# Syno_Ver3_0.net
KiCad netlist of a schematic drawn in EAGLE
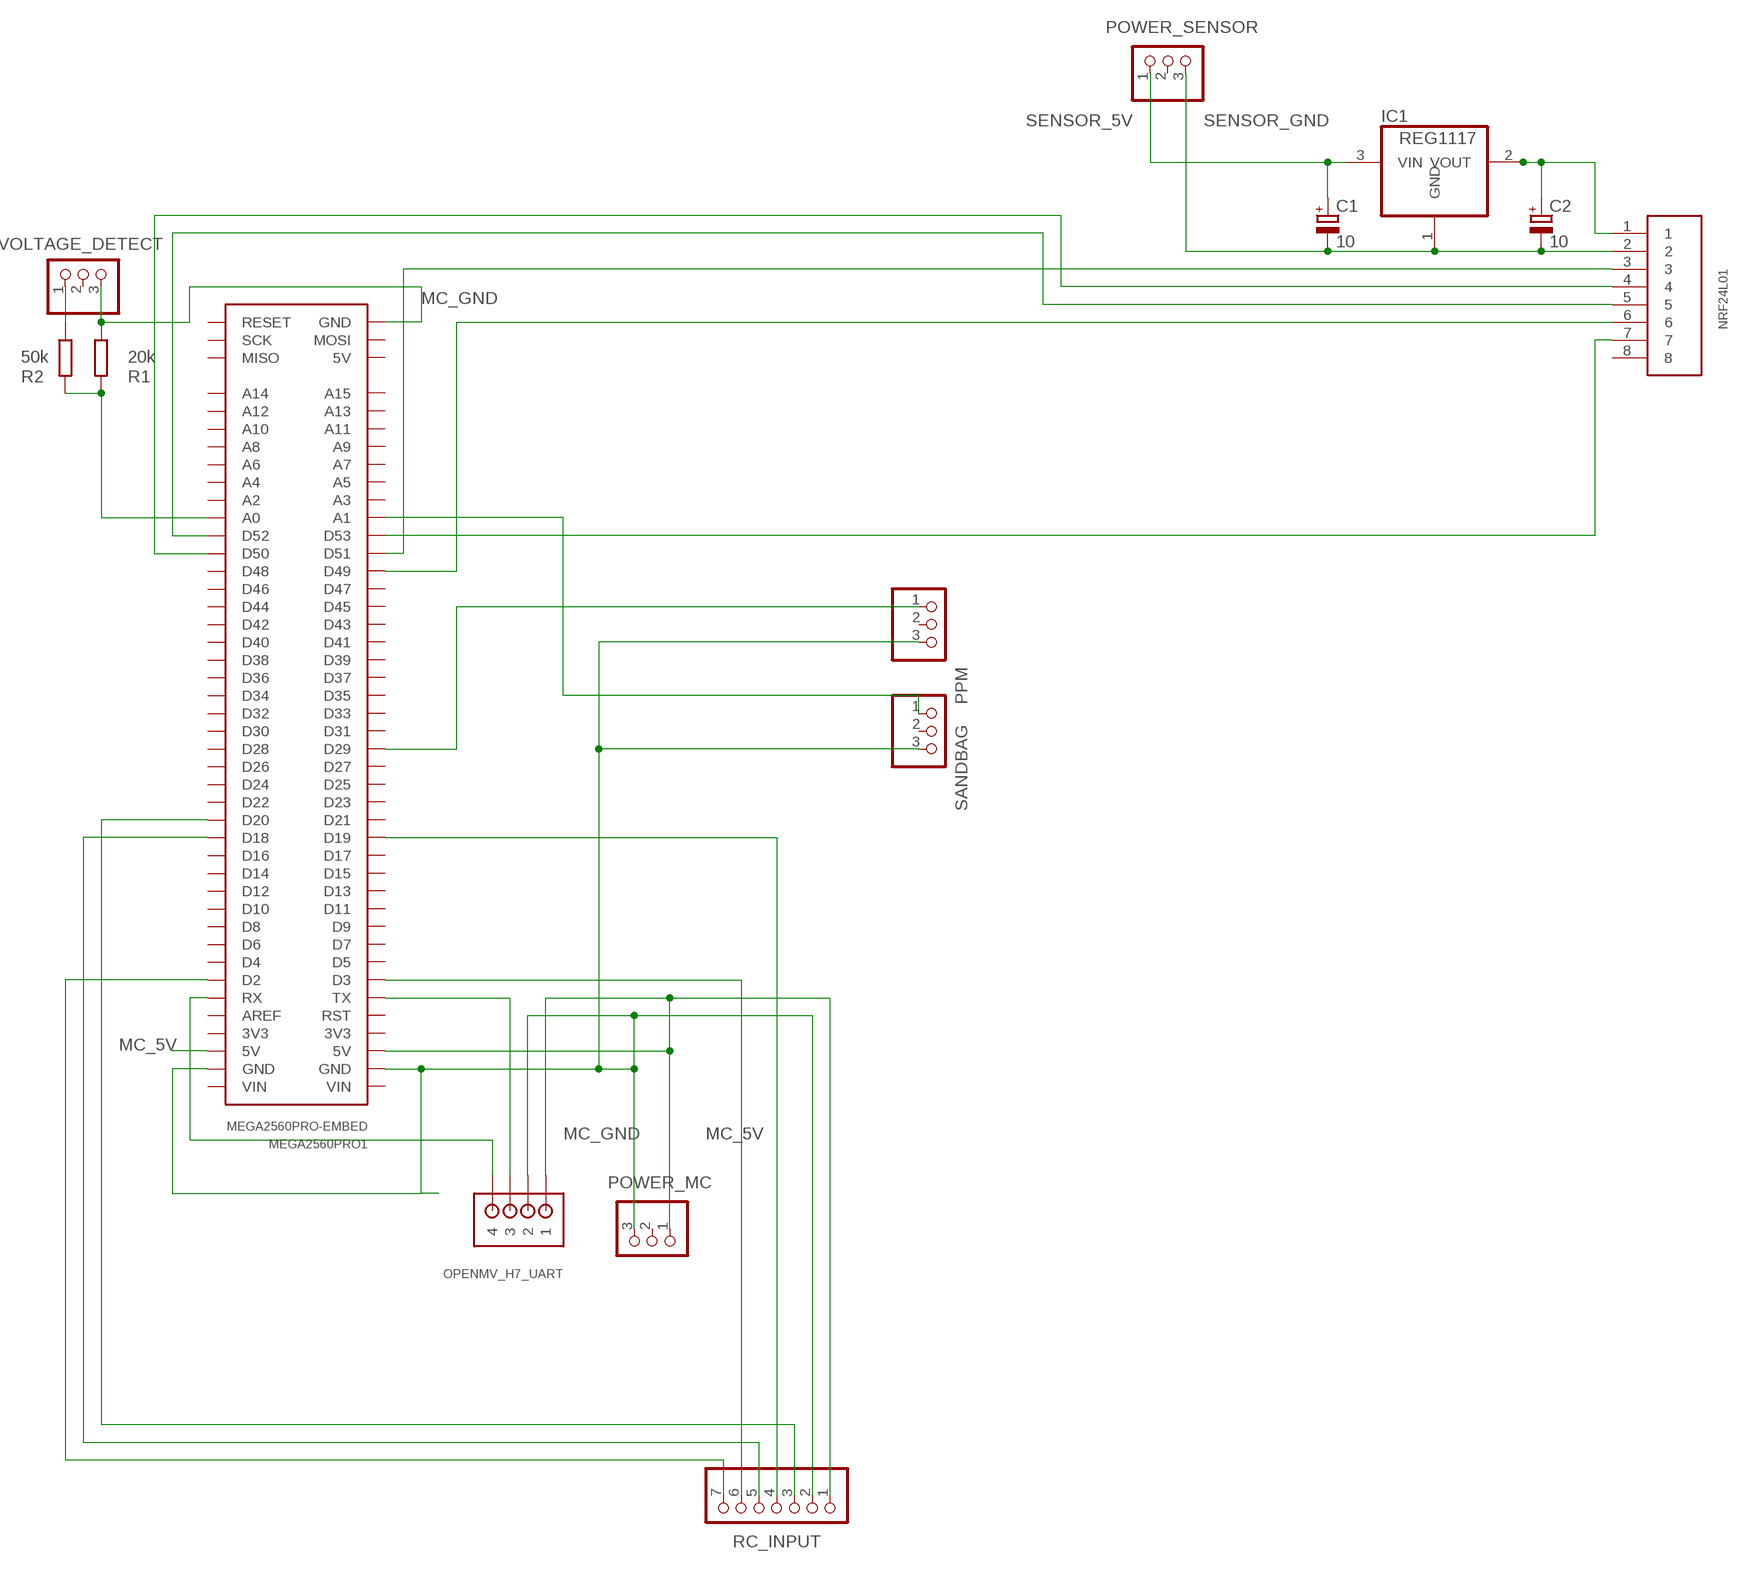
[diagram p0: schematic, sheet 1]

(export (version "E")
  (design (tool "Eeschema 10.0.6"))
  (components
    (comp (ref "C1")
      (value "10")
      (footprint "eagle-import:E1,8-4")
      (libsource (lib "eagle-import") (part "CPOL-EUE1.8-4"))
    )
    (comp (ref "C2")
      (value "10")
      (footprint "eagle-import:E1,8-4")
      (libsource (lib "eagle-import") (part "CPOL-EUE1.8-4"))
    )
    (comp (ref "IC1")
      (value "REG1117")
      (footprint "eagle-import:SOT223")
      (libsource (lib "eagle-import") (part "REG1117"))
    )
    (comp (ref "MEGA2560PRO1")
      (value "MEGA2560PRO-EMBED")
      (footprint "eagle-import:MEGA2560PRO-EMBED")
      (libsource (lib "eagle-import") (part "MEGA2560PRO-EMBED"))
    )
    (comp (ref "NRF24L01")
      (value "8PIN")
      (footprint "eagle-import:B8B-PH-K-S")
      (libsource (lib "eagle-import") (part "8PIN"))
    )
    (comp (ref "OPENMV_H7_UART")
      (value "JST-PH_4-PIN_HEADER")
      (footprint "eagle-import:JST_B4B-PH_HEADER")
      (libsource (lib "eagle-import") (part "JST-PH_4-PIN_HEADER"))
    )
    (comp (ref "POWER_MC")
      (value "PINHD-1X3/90")
      (footprint "eagle-import:1X03_90")
      (libsource (lib "eagle-import") (part "PINHD-1X3/90"))
    )
    (comp (ref "POWER_SENSOR")
      (value "PINHD-1X3/90")
      (footprint "eagle-import:1X03_90")
      (libsource (lib "eagle-import") (part "PINHD-1X3/90"))
    )
    (comp (ref "PPM")
      (value "PINHD-1X3/90")
      (footprint "eagle-import:1X03_90")
      (libsource (lib "eagle-import") (part "PINHD-1X3/90"))
    )
    (comp (ref "R1")
      (value "20k")
      (footprint "eagle-import:0204_5")
      (libsource (lib "eagle-import") (part "R-EU_0204/5"))
    )
    (comp (ref "R2")
      (value "50k")
      (footprint "eagle-import:0204_5")
      (libsource (lib "eagle-import") (part "R-EU_0204/5"))
    )
    (comp (ref "RC_INPUT")
      (value "PINHD-1X7/90")
      (footprint "eagle-import:1X07_90")
      (libsource (lib "eagle-import") (part "PINHD-1X7/90"))
    )
    (comp (ref "SANDBAG")
      (value "PINHD-1X3/90")
      (footprint "eagle-import:1X03_90")
      (libsource (lib "eagle-import") (part "PINHD-1X3/90"))
    )
    (comp (ref "VOLTAGE_DETECT")
      (value "PINHD-1X3/90")
      (footprint "eagle-import:1X03_90")
      (libsource (lib "eagle-import") (part "PINHD-1X3/90"))
    )
  )
  (nets
    (net (code "1") (name "/MC_5V") (class "Default")
      (node (ref "MEGA2560PRO1") (pin "5V@1") (pinfunction "5V_5V@1") (pintype "bidirectional"))
      (node (ref "MEGA2560PRO1") (pin "5V@2") (pinfunction "5V_5V@2") (pintype "bidirectional"))
      (node (ref "OPENMV_H7_UART") (pin "P1") (pinfunction "1_P1") (pintype "bidirectional"))
      (node (ref "POWER_MC") (pin "1") (pinfunction "1_1") (pintype "passive"))
      (node (ref "RC_INPUT") (pin "1") (pinfunction "1_1") (pintype "passive"))
    )
    (net (code "2") (name "/MC_GND") (class "Default")
      (node (ref "MEGA2560PRO1") (pin "GND@1") (pinfunction "GND_GND@1") (pintype "bidirectional"))
      (node (ref "MEGA2560PRO1") (pin "GND@2") (pinfunction "GND_GND@2") (pintype "bidirectional"))
      (node (ref "MEGA2560PRO1") (pin "GND@3") (pinfunction "GND_GND@3") (pintype "bidirectional"))
      (node (ref "OPENMV_H7_UART") (pin "P2") (pinfunction "2_P2") (pintype "bidirectional"))
      (node (ref "POWER_MC") (pin "3") (pinfunction "3_3") (pintype "passive"))
      (node (ref "PPM") (pin "3") (pinfunction "3_3") (pintype "passive"))
      (node (ref "R1") (pin "1") (pinfunction "1_1") (pintype "passive"))
      (node (ref "RC_INPUT") (pin "2") (pinfunction "2_2") (pintype "passive"))
      (node (ref "SANDBAG") (pin "3") (pinfunction "3_3") (pintype "passive"))
      (node (ref "VOLTAGE_DETECT") (pin "3") (pinfunction "3_3") (pintype "passive"))
    )
    (net (code "3") (name "/SENSOR_5V") (class "Default")
      (node (ref "C1") (pin "+") (pinfunction "+_+") (pintype "passive"))
      (node (ref "IC1") (pin "3") (pinfunction "VIN_3") (pintype "input"))
      (node (ref "POWER_SENSOR") (pin "1") (pinfunction "1_1") (pintype "passive"))
    )
    (net (code "4") (name "/SENSOR_GND") (class "Default")
      (node (ref "C1") (pin "-") (pinfunction "-_-") (pintype "passive"))
      (node (ref "C2") (pin "-") (pinfunction "-_-") (pintype "passive"))
      (node (ref "IC1") (pin "1") (pinfunction "GND_1") (pintype "power_in"))
      (node (ref "NRF24L01") (pin "2") (pinfunction "2_2") (pintype "bidirectional"))
      (node (ref "POWER_SENSOR") (pin "3") (pinfunction "3_3") (pintype "passive"))
    )
    (net (code "5") (name "Net-(IC1-VOUT)") (class "Default")
      (node (ref "C2") (pin "+") (pinfunction "+_+") (pintype "passive"))
      (node (ref "IC1") (pin "2") (pinfunction "VOUT_2") (pintype "output"))
      (node (ref "NRF24L01") (pin "1") (pinfunction "1_1") (pintype "bidirectional"))
    )
    (net (code "6") (name "Net-(MEGA2560PRO1-PadA0)") (class "Default")
      (node (ref "MEGA2560PRO1") (pin "A0") (pinfunction "A0_A0") (pintype "bidirectional"))
      (node (ref "R1") (pin "2") (pinfunction "2_2") (pintype "passive"))
      (node (ref "R2") (pin "2") (pinfunction "2_2") (pintype "passive"))
    )
    (net (code "7") (name "Net-(MEGA2560PRO1-PadA1)") (class "Default")
      (node (ref "MEGA2560PRO1") (pin "A1") (pinfunction "A1_A1") (pintype "bidirectional"))
      (node (ref "SANDBAG") (pin "1") (pinfunction "1_1") (pintype "passive"))
    )
    (net (code "8") (name "Net-(MEGA2560PRO1-PadD2)") (class "Default")
      (node (ref "MEGA2560PRO1") (pin "D2") (pinfunction "D2_D2") (pintype "bidirectional"))
      (node (ref "RC_INPUT") (pin "7") (pinfunction "7_7") (pintype "passive"))
    )
    (net (code "9") (name "Net-(MEGA2560PRO1-PadD3)") (class "Default")
      (node (ref "MEGA2560PRO1") (pin "D3") (pinfunction "D3_D3") (pintype "bidirectional"))
      (node (ref "RC_INPUT") (pin "6") (pinfunction "6_6") (pintype "passive"))
    )
    (net (code "10") (name "Net-(MEGA2560PRO1-PadD18)") (class "Default")
      (node (ref "MEGA2560PRO1") (pin "D18") (pinfunction "D18_D18") (pintype "bidirectional"))
      (node (ref "RC_INPUT") (pin "5") (pinfunction "5_5") (pintype "passive"))
    )
    (net (code "11") (name "Net-(MEGA2560PRO1-PadD19)") (class "Default")
      (node (ref "MEGA2560PRO1") (pin "D19") (pinfunction "D19_D19") (pintype "bidirectional"))
      (node (ref "RC_INPUT") (pin "4") (pinfunction "4_4") (pintype "passive"))
    )
    (net (code "12") (name "Net-(MEGA2560PRO1-PadD20)") (class "Default")
      (node (ref "MEGA2560PRO1") (pin "D20") (pinfunction "D20_D20") (pintype "bidirectional"))
      (node (ref "RC_INPUT") (pin "3") (pinfunction "3_3") (pintype "passive"))
    )
    (net (code "13") (name "Net-(MEGA2560PRO1-PadD29)") (class "Default")
      (node (ref "MEGA2560PRO1") (pin "D29") (pinfunction "D29_D29") (pintype "bidirectional"))
      (node (ref "PPM") (pin "1") (pinfunction "1_1") (pintype "passive"))
    )
    (net (code "14") (name "Net-(MEGA2560PRO1-PadD49)") (class "Default")
      (node (ref "MEGA2560PRO1") (pin "D49") (pinfunction "D49_D49") (pintype "bidirectional"))
      (node (ref "NRF24L01") (pin "6") (pinfunction "6_6") (pintype "bidirectional"))
    )
    (net (code "15") (name "Net-(MEGA2560PRO1-PadD50)") (class "Default")
      (node (ref "MEGA2560PRO1") (pin "D50") (pinfunction "D50_D50") (pintype "bidirectional"))
      (node (ref "NRF24L01") (pin "4") (pinfunction "4_4") (pintype "bidirectional"))
    )
    (net (code "16") (name "Net-(MEGA2560PRO1-PadD51)") (class "Default")
      (node (ref "MEGA2560PRO1") (pin "D51") (pinfunction "D51_D51") (pintype "bidirectional"))
      (node (ref "NRF24L01") (pin "3") (pinfunction "3_3") (pintype "bidirectional"))
    )
    (net (code "17") (name "Net-(MEGA2560PRO1-PadD52)") (class "Default")
      (node (ref "MEGA2560PRO1") (pin "D52") (pinfunction "D52_D52") (pintype "bidirectional"))
      (node (ref "NRF24L01") (pin "5") (pinfunction "5_5") (pintype "bidirectional"))
    )
    (net (code "18") (name "Net-(MEGA2560PRO1-PadD53)") (class "Default")
      (node (ref "MEGA2560PRO1") (pin "D53") (pinfunction "D53_D53") (pintype "bidirectional"))
      (node (ref "NRF24L01") (pin "7") (pinfunction "7_7") (pintype "bidirectional"))
    )
    (net (code "19") (name "Net-(OPENMV_H7_UART-3)") (class "Default")
      (node (ref "MEGA2560PRO1") (pin "TX") (pinfunction "TX_TX") (pintype "bidirectional"))
      (node (ref "OPENMV_H7_UART") (pin "P3") (pinfunction "3_P3") (pintype "bidirectional"))
    )
    (net (code "20") (name "Net-(OPENMV_H7_UART-4)") (class "Default")
      (node (ref "MEGA2560PRO1") (pin "RX") (pinfunction "RX_RX") (pintype "bidirectional"))
      (node (ref "OPENMV_H7_UART") (pin "P4") (pinfunction "4_P4") (pintype "bidirectional"))
    )
    (net (code "21") (name "Net-(R2-Pad1)") (class "Default")
      (node (ref "R2") (pin "1") (pinfunction "1_1") (pintype "passive"))
      (node (ref "VOLTAGE_DETECT") (pin "1") (pinfunction "1_1") (pintype "passive"))
    )
    (net (code "22") (name "unconnected-(MEGA2560PRO1-3V3-Pad3V3@1)") (class "Default")
      (node (ref "MEGA2560PRO1") (pin "3V3@1") (pinfunction "3V3_3V3@1") (pintype "bidirectional"))
    )
    (net (code "23") (name "unconnected-(MEGA2560PRO1-3V3-Pad3V3@2)") (class "Default")
      (node (ref "MEGA2560PRO1") (pin "3V3@2") (pinfunction "3V3_3V3@2") (pintype "bidirectional"))
    )
    (net (code "24") (name "unconnected-(MEGA2560PRO1-5V-Pad5V@3)") (class "Default")
      (node (ref "MEGA2560PRO1") (pin "5V@3") (pinfunction "5V_5V@3") (pintype "bidirectional"))
    )
    (net (code "25") (name "unconnected-(MEGA2560PRO1-PadA2)") (class "Default")
      (node (ref "MEGA2560PRO1") (pin "A2") (pinfunction "A2_A2") (pintype "bidirectional"))
    )
    (net (code "26") (name "unconnected-(MEGA2560PRO1-PadA3)") (class "Default")
      (node (ref "MEGA2560PRO1") (pin "A3") (pinfunction "A3_A3") (pintype "bidirectional"))
    )
    (net (code "27") (name "unconnected-(MEGA2560PRO1-PadA4)") (class "Default")
      (node (ref "MEGA2560PRO1") (pin "A4") (pinfunction "A4_A4") (pintype "bidirectional"))
    )
    (net (code "28") (name "unconnected-(MEGA2560PRO1-PadA5)") (class "Default")
      (node (ref "MEGA2560PRO1") (pin "A5") (pinfunction "A5_A5") (pintype "bidirectional"))
    )
    (net (code "29") (name "unconnected-(MEGA2560PRO1-PadA6)") (class "Default")
      (node (ref "MEGA2560PRO1") (pin "A6") (pinfunction "A6_A6") (pintype "bidirectional"))
    )
    (net (code "30") (name "unconnected-(MEGA2560PRO1-PadA7)") (class "Default")
      (node (ref "MEGA2560PRO1") (pin "A7") (pinfunction "A7_A7") (pintype "bidirectional"))
    )
    (net (code "31") (name "unconnected-(MEGA2560PRO1-PadA8)") (class "Default")
      (node (ref "MEGA2560PRO1") (pin "A8") (pinfunction "A8_A8") (pintype "bidirectional"))
    )
    (net (code "32") (name "unconnected-(MEGA2560PRO1-PadA9)") (class "Default")
      (node (ref "MEGA2560PRO1") (pin "A9") (pinfunction "A9_A9") (pintype "bidirectional"))
    )
    (net (code "33") (name "unconnected-(MEGA2560PRO1-PadA10)") (class "Default")
      (node (ref "MEGA2560PRO1") (pin "A10") (pinfunction "A10_A10") (pintype "bidirectional"))
    )
    (net (code "34") (name "unconnected-(MEGA2560PRO1-PadA11)") (class "Default")
      (node (ref "MEGA2560PRO1") (pin "A11") (pinfunction "A11_A11") (pintype "bidirectional"))
    )
    (net (code "35") (name "unconnected-(MEGA2560PRO1-PadA12)") (class "Default")
      (node (ref "MEGA2560PRO1") (pin "A12") (pinfunction "A12_A12") (pintype "bidirectional"))
    )
    (net (code "36") (name "unconnected-(MEGA2560PRO1-PadA13)") (class "Default")
      (node (ref "MEGA2560PRO1") (pin "A13") (pinfunction "A13_A13") (pintype "bidirectional"))
    )
    (net (code "37") (name "unconnected-(MEGA2560PRO1-PadA14)") (class "Default")
      (node (ref "MEGA2560PRO1") (pin "A14") (pinfunction "A14_A14") (pintype "bidirectional"))
    )
    (net (code "38") (name "unconnected-(MEGA2560PRO1-PadA15)") (class "Default")
      (node (ref "MEGA2560PRO1") (pin "A15") (pinfunction "A15_A15") (pintype "bidirectional"))
    )
    (net (code "39") (name "unconnected-(MEGA2560PRO1-PadAREF)") (class "Default")
      (node (ref "MEGA2560PRO1") (pin "AREF") (pinfunction "AREF_AREF") (pintype "bidirectional"))
    )
    (net (code "40") (name "unconnected-(MEGA2560PRO1-PadD4)") (class "Default")
      (node (ref "MEGA2560PRO1") (pin "D4") (pinfunction "D4_D4") (pintype "bidirectional"))
    )
    (net (code "41") (name "unconnected-(MEGA2560PRO1-PadD5)") (class "Default")
      (node (ref "MEGA2560PRO1") (pin "D5") (pinfunction "D5_D5") (pintype "bidirectional"))
    )
    (net (code "42") (name "unconnected-(MEGA2560PRO1-PadD6)") (class "Default")
      (node (ref "MEGA2560PRO1") (pin "D6") (pinfunction "D6_D6") (pintype "bidirectional"))
    )
    (net (code "43") (name "unconnected-(MEGA2560PRO1-PadD7)") (class "Default")
      (node (ref "MEGA2560PRO1") (pin "D7") (pinfunction "D7_D7") (pintype "bidirectional"))
    )
    (net (code "44") (name "unconnected-(MEGA2560PRO1-PadD8)") (class "Default")
      (node (ref "MEGA2560PRO1") (pin "D8") (pinfunction "D8_D8") (pintype "bidirectional"))
    )
    (net (code "45") (name "unconnected-(MEGA2560PRO1-PadD9)") (class "Default")
      (node (ref "MEGA2560PRO1") (pin "D9") (pinfunction "D9_D9") (pintype "bidirectional"))
    )
    (net (code "46") (name "unconnected-(MEGA2560PRO1-PadD10)") (class "Default")
      (node (ref "MEGA2560PRO1") (pin "D10") (pinfunction "D10_D10") (pintype "bidirectional"))
    )
    (net (code "47") (name "unconnected-(MEGA2560PRO1-PadD11)") (class "Default")
      (node (ref "MEGA2560PRO1") (pin "D11") (pinfunction "D11_D11") (pintype "bidirectional"))
    )
    (net (code "48") (name "unconnected-(MEGA2560PRO1-PadD12)") (class "Default")
      (node (ref "MEGA2560PRO1") (pin "D12") (pinfunction "D12_D12") (pintype "bidirectional"))
    )
    (net (code "49") (name "unconnected-(MEGA2560PRO1-PadD13)") (class "Default")
      (node (ref "MEGA2560PRO1") (pin "D13") (pinfunction "D13_D13") (pintype "bidirectional"))
    )
    (net (code "50") (name "unconnected-(MEGA2560PRO1-PadD14)") (class "Default")
      (node (ref "MEGA2560PRO1") (pin "D14") (pinfunction "D14_D14") (pintype "bidirectional"))
    )
    (net (code "51") (name "unconnected-(MEGA2560PRO1-PadD15)") (class "Default")
      (node (ref "MEGA2560PRO1") (pin "D15") (pinfunction "D15_D15") (pintype "bidirectional"))
    )
    (net (code "52") (name "unconnected-(MEGA2560PRO1-PadD16)") (class "Default")
      (node (ref "MEGA2560PRO1") (pin "D16") (pinfunction "D16_D16") (pintype "bidirectional"))
    )
    (net (code "53") (name "unconnected-(MEGA2560PRO1-PadD17)") (class "Default")
      (node (ref "MEGA2560PRO1") (pin "D17") (pinfunction "D17_D17") (pintype "bidirectional"))
    )
    (net (code "54") (name "unconnected-(MEGA2560PRO1-PadD21)") (class "Default")
      (node (ref "MEGA2560PRO1") (pin "D21") (pinfunction "D21_D21") (pintype "bidirectional"))
    )
    (net (code "55") (name "unconnected-(MEGA2560PRO1-PadD22)") (class "Default")
      (node (ref "MEGA2560PRO1") (pin "D22") (pinfunction "D22_D22") (pintype "bidirectional"))
    )
    (net (code "56") (name "unconnected-(MEGA2560PRO1-PadD23)") (class "Default")
      (node (ref "MEGA2560PRO1") (pin "D23") (pinfunction "D23_D23") (pintype "bidirectional"))
    )
    (net (code "57") (name "unconnected-(MEGA2560PRO1-PadD24)") (class "Default")
      (node (ref "MEGA2560PRO1") (pin "D24") (pinfunction "D24_D24") (pintype "bidirectional"))
    )
    (net (code "58") (name "unconnected-(MEGA2560PRO1-PadD25)") (class "Default")
      (node (ref "MEGA2560PRO1") (pin "D25") (pinfunction "D25_D25") (pintype "bidirectional"))
    )
    (net (code "59") (name "unconnected-(MEGA2560PRO1-PadD26)") (class "Default")
      (node (ref "MEGA2560PRO1") (pin "D26") (pinfunction "D26_D26") (pintype "bidirectional"))
    )
    (net (code "60") (name "unconnected-(MEGA2560PRO1-PadD27)") (class "Default")
      (node (ref "MEGA2560PRO1") (pin "D27") (pinfunction "D27_D27") (pintype "bidirectional"))
    )
    (net (code "61") (name "unconnected-(MEGA2560PRO1-PadD28)") (class "Default")
      (node (ref "MEGA2560PRO1") (pin "D28") (pinfunction "D28_D28") (pintype "bidirectional"))
    )
    (net (code "62") (name "unconnected-(MEGA2560PRO1-PadD30)") (class "Default")
      (node (ref "MEGA2560PRO1") (pin "D30") (pinfunction "D30_D30") (pintype "bidirectional"))
    )
    (net (code "63") (name "unconnected-(MEGA2560PRO1-PadD31)") (class "Default")
      (node (ref "MEGA2560PRO1") (pin "D31") (pinfunction "D31_D31") (pintype "bidirectional"))
    )
    (net (code "64") (name "unconnected-(MEGA2560PRO1-PadD32)") (class "Default")
      (node (ref "MEGA2560PRO1") (pin "D32") (pinfunction "D32_D32") (pintype "bidirectional"))
    )
    (net (code "65") (name "unconnected-(MEGA2560PRO1-PadD33)") (class "Default")
      (node (ref "MEGA2560PRO1") (pin "D33") (pinfunction "D33_D33") (pintype "bidirectional"))
    )
    (net (code "66") (name "unconnected-(MEGA2560PRO1-PadD34)") (class "Default")
      (node (ref "MEGA2560PRO1") (pin "D34") (pinfunction "D34_D34") (pintype "bidirectional"))
    )
    (net (code "67") (name "unconnected-(MEGA2560PRO1-PadD35)") (class "Default")
      (node (ref "MEGA2560PRO1") (pin "D35") (pinfunction "D35_D35") (pintype "bidirectional"))
    )
    (net (code "68") (name "unconnected-(MEGA2560PRO1-PadD36)") (class "Default")
      (node (ref "MEGA2560PRO1") (pin "D36") (pinfunction "D36_D36") (pintype "bidirectional"))
    )
    (net (code "69") (name "unconnected-(MEGA2560PRO1-PadD37)") (class "Default")
      (node (ref "MEGA2560PRO1") (pin "D37") (pinfunction "D37_D37") (pintype "bidirectional"))
    )
    (net (code "70") (name "unconnected-(MEGA2560PRO1-PadD38)") (class "Default")
      (node (ref "MEGA2560PRO1") (pin "D38") (pinfunction "D38_D38") (pintype "bidirectional"))
    )
    (net (code "71") (name "unconnected-(MEGA2560PRO1-PadD39)") (class "Default")
      (node (ref "MEGA2560PRO1") (pin "D39") (pinfunction "D39_D39") (pintype "bidirectional"))
    )
    (net (code "72") (name "unconnected-(MEGA2560PRO1-PadD40)") (class "Default")
      (node (ref "MEGA2560PRO1") (pin "D40") (pinfunction "D40_D40") (pintype "bidirectional"))
    )
    (net (code "73") (name "unconnected-(MEGA2560PRO1-PadD41)") (class "Default")
      (node (ref "MEGA2560PRO1") (pin "D41") (pinfunction "D41_D41") (pintype "bidirectional"))
    )
    (net (code "74") (name "unconnected-(MEGA2560PRO1-PadD42)") (class "Default")
      (node (ref "MEGA2560PRO1") (pin "D42") (pinfunction "D42_D42") (pintype "bidirectional"))
    )
    (net (code "75") (name "unconnected-(MEGA2560PRO1-PadD43)") (class "Default")
      (node (ref "MEGA2560PRO1") (pin "D43") (pinfunction "D43_D43") (pintype "bidirectional"))
    )
    (net (code "76") (name "unconnected-(MEGA2560PRO1-PadD44)") (class "Default")
      (node (ref "MEGA2560PRO1") (pin "D44") (pinfunction "D44_D44") (pintype "bidirectional"))
    )
    (net (code "77") (name "unconnected-(MEGA2560PRO1-PadD45)") (class "Default")
      (node (ref "MEGA2560PRO1") (pin "D45") (pinfunction "D45_D45") (pintype "bidirectional"))
    )
    (net (code "78") (name "unconnected-(MEGA2560PRO1-PadD46)") (class "Default")
      (node (ref "MEGA2560PRO1") (pin "D46") (pinfunction "D46_D46") (pintype "bidirectional"))
    )
    (net (code "79") (name "unconnected-(MEGA2560PRO1-PadD47)") (class "Default")
      (node (ref "MEGA2560PRO1") (pin "D47") (pinfunction "D47_D47") (pintype "bidirectional"))
    )
    (net (code "80") (name "unconnected-(MEGA2560PRO1-PadD48)") (class "Default")
      (node (ref "MEGA2560PRO1") (pin "D48") (pinfunction "D48_D48") (pintype "bidirectional"))
    )
    (net (code "81") (name "unconnected-(MEGA2560PRO1-PadMISO)") (class "Default")
      (node (ref "MEGA2560PRO1") (pin "MISO") (pinfunction "MISO_MISO") (pintype "bidirectional"))
    )
    (net (code "82") (name "unconnected-(MEGA2560PRO1-PadMOSI)") (class "Default")
      (node (ref "MEGA2560PRO1") (pin "MOSI") (pinfunction "MOSI_MOSI") (pintype "bidirectional"))
    )
    (net (code "83") (name "unconnected-(MEGA2560PRO1-PadRESET)") (class "Default")
      (node (ref "MEGA2560PRO1") (pin "RESET") (pinfunction "RESET_RESET") (pintype "bidirectional"))
    )
    (net (code "84") (name "unconnected-(MEGA2560PRO1-PadRST)") (class "Default")
      (node (ref "MEGA2560PRO1") (pin "RST") (pinfunction "RST_RST") (pintype "bidirectional"))
    )
    (net (code "85") (name "unconnected-(MEGA2560PRO1-PadSCK)") (class "Default")
      (node (ref "MEGA2560PRO1") (pin "SCK") (pinfunction "SCK_SCK") (pintype "bidirectional"))
    )
    (net (code "86") (name "unconnected-(MEGA2560PRO1-VIN-PadVIN@1)") (class "Default")
      (node (ref "MEGA2560PRO1") (pin "VIN@1") (pinfunction "VIN_VIN@1") (pintype "bidirectional"))
    )
    (net (code "87") (name "unconnected-(MEGA2560PRO1-VIN-PadVIN@2)") (class "Default")
      (node (ref "MEGA2560PRO1") (pin "VIN@2") (pinfunction "VIN_VIN@2") (pintype "bidirectional"))
    )
    (net (code "88") (name "unconnected-(NRF24L01-Pad8)") (class "Default")
      (node (ref "NRF24L01") (pin "8") (pinfunction "8_8") (pintype "bidirectional"))
    )
    (net (code "89") (name "unconnected-(POWER_MC-Pad2)") (class "Default")
      (node (ref "POWER_MC") (pin "2") (pinfunction "2_2") (pintype "passive"))
    )
    (net (code "90") (name "unconnected-(POWER_SENSOR-Pad2)") (class "Default")
      (node (ref "POWER_SENSOR") (pin "2") (pinfunction "2_2") (pintype "passive"))
    )
    (net (code "91") (name "unconnected-(PPM-Pad2)") (class "Default")
      (node (ref "PPM") (pin "2") (pinfunction "2_2") (pintype "passive"))
    )
    (net (code "92") (name "unconnected-(SANDBAG-Pad2)") (class "Default")
      (node (ref "SANDBAG") (pin "2") (pinfunction "2_2") (pintype "passive"))
    )
    (net (code "93") (name "unconnected-(VOLTAGE_DETECT-Pad2)") (class "Default")
      (node (ref "VOLTAGE_DETECT") (pin "2") (pinfunction "2_2") (pintype "passive"))
    )
  )
)
